# OptimuxPrimeEnlarged.net
KiCad netlist of a schematic drawn in EAGLE
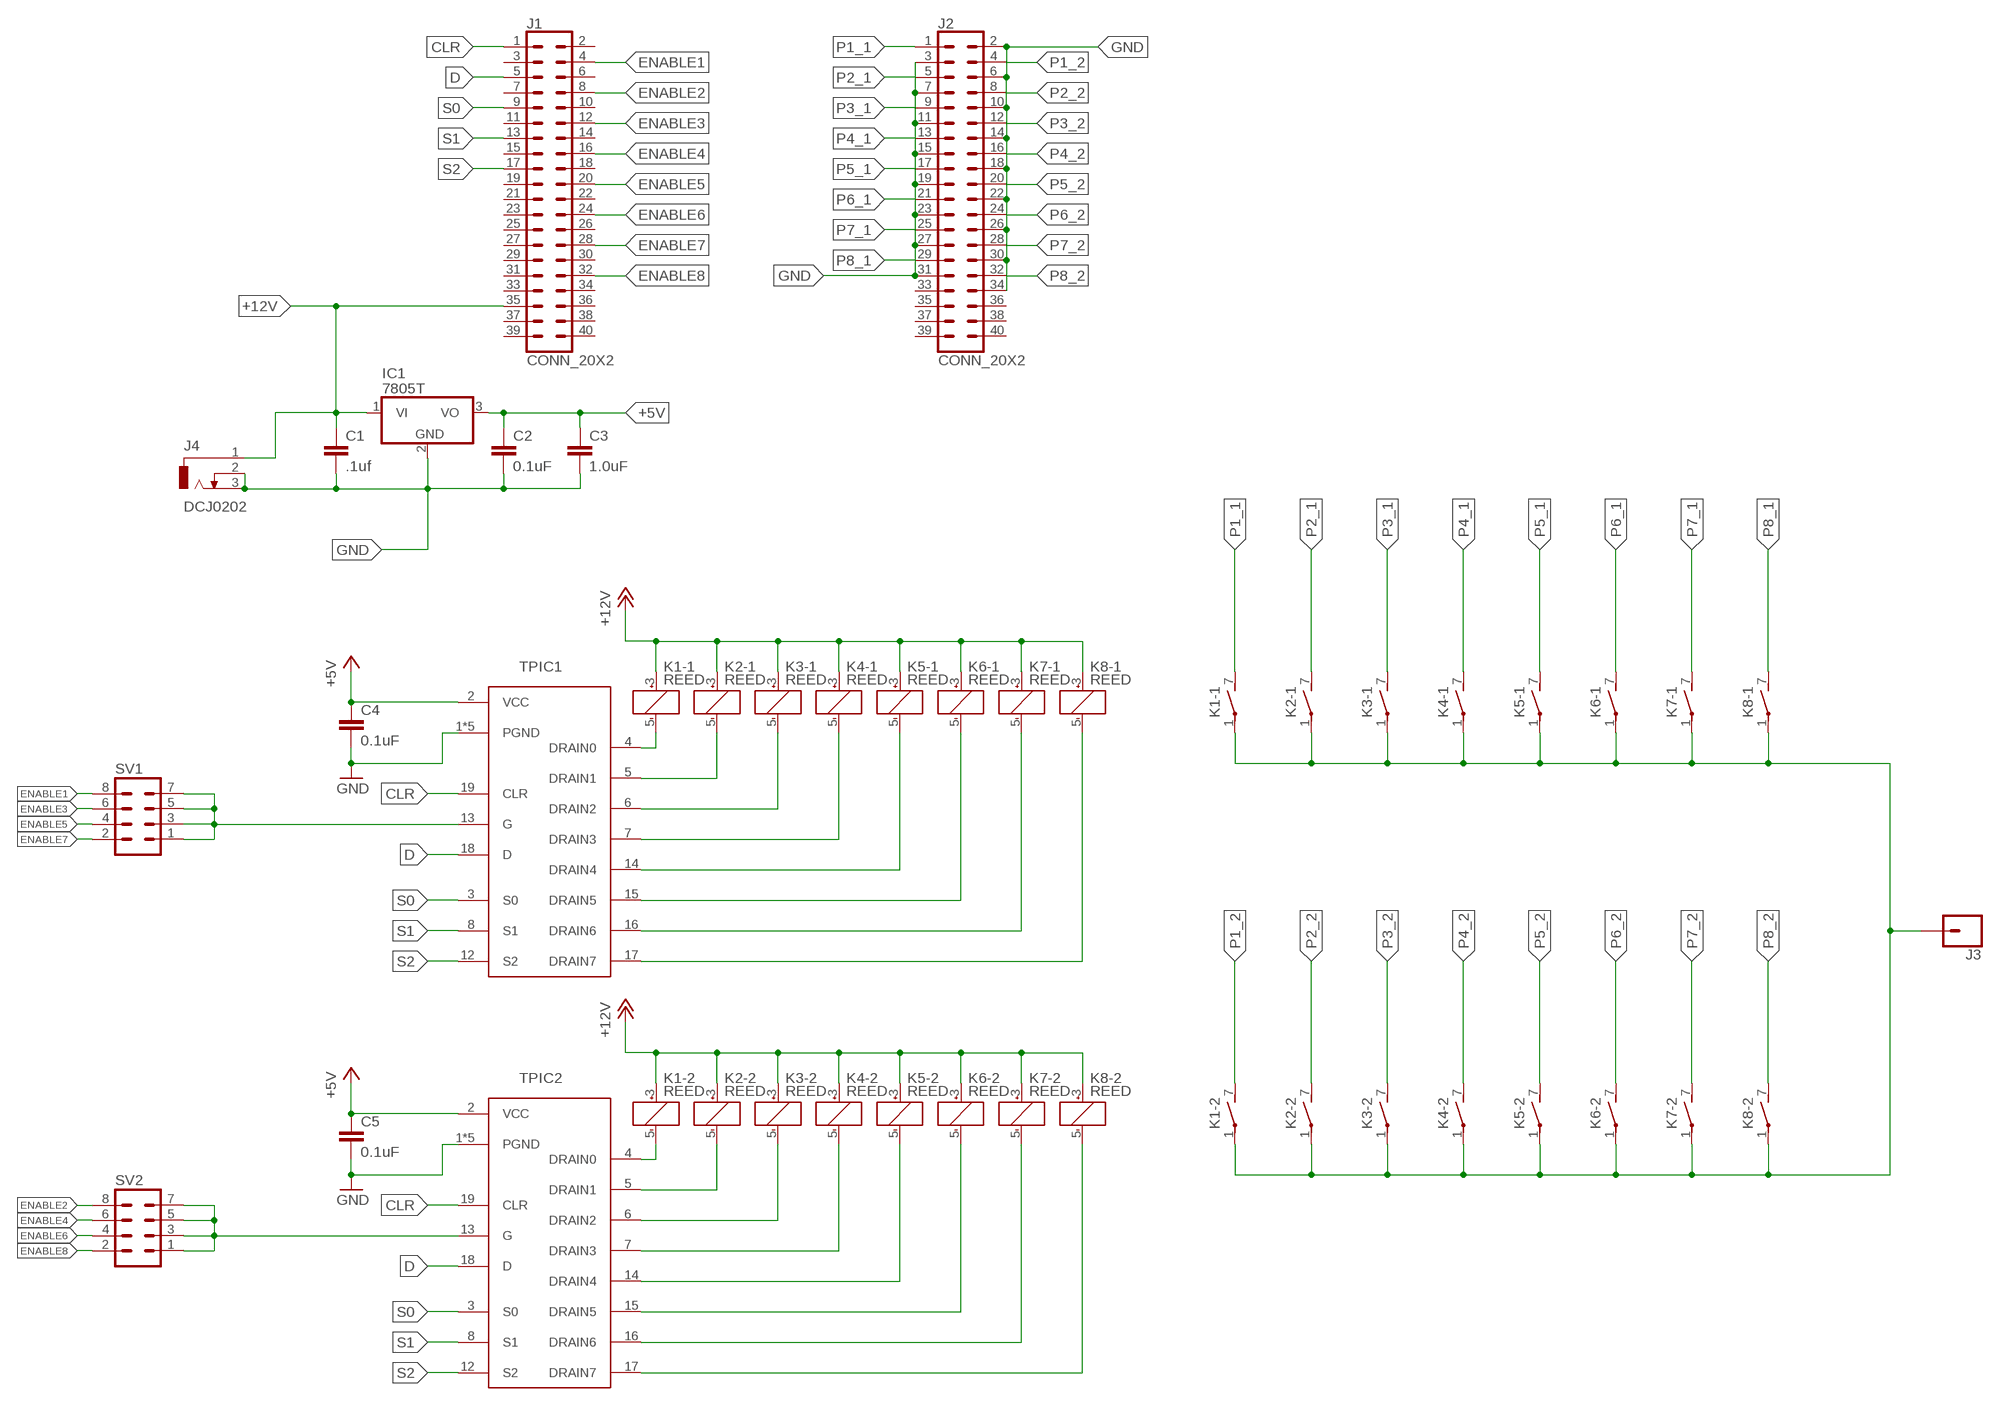
[diagram p0: schematic, sheet 1]

(export (version "E")
  (design (tool "Eeschema 10.0.6"))
  (components
    (comp (ref "C1")
      (value ".1uf")
      (footprint "eagle-import:0805")
      (libsource (lib "eagle-import") (part "1.0UF-0805-25V-(+80/-20%)"))
    )
    (comp (ref "C2")
      (value "0.1uF")
      (footprint "eagle-import:0805")
      (libsource (lib "eagle-import") (part "1.0UF-0805-25V-(+80/-20%)"))
    )
    (comp (ref "C3")
      (value "1.0uF")
      (footprint "eagle-import:0805")
      (libsource (lib "eagle-import") (part "1.0UF-0805-25V-(+80/-20%)"))
    )
    (comp (ref "C4")
      (value "0.1uF")
      (footprint "eagle-import:0805")
      (libsource (lib "eagle-import") (part "1.0UF-0805-25V-(+80/-20%)"))
    )
    (comp (ref "C5")
      (value "0.1uF")
      (footprint "eagle-import:0805")
      (libsource (lib "eagle-import") (part "1.0UF-0805-25V-(+80/-20%)"))
    )
    (comp (ref "IC1")
      (value "7805T")
      (footprint "eagle-import:TO220H")
      (libsource (lib "eagle-import") (part "78T05"))
    )
    (comp (ref "J1")
      (value "CONN_20X2")
      (footprint "eagle-import:2X20")
      (libsource (lib "eagle-import") (part "CONN_20X2"))
    )
    (comp (ref "J2")
      (value "CONN_20X2")
      (footprint "eagle-import:2X20")
      (libsource (lib "eagle-import") (part "CONN_20X2"))
    )
    (comp (ref "J3")
      (value "CONN_01")
      (footprint "eagle-import:1X01")
      (libsource (lib "eagle-import") (part "CONN_01"))
    )
    (comp (ref "J4")
      (value "DCJ0202")
      (footprint "eagle-import:DCJ0202")
      (libsource (lib "eagle-import") (part "DCJ0202"))
    )
    (comp (ref "K1-1")
      (value "REED")
      (footprint "eagle-import:REED")
      (libsource (lib "eagle-import") (part "REED"))
    )
    (comp (ref "K1-2")
      (value "REED")
      (footprint "eagle-import:REED")
      (libsource (lib "eagle-import") (part "REED"))
    )
    (comp (ref "K2-1")
      (value "REED")
      (footprint "eagle-import:REED")
      (libsource (lib "eagle-import") (part "REED"))
    )
    (comp (ref "K2-2")
      (value "REED")
      (footprint "eagle-import:REED")
      (libsource (lib "eagle-import") (part "REED"))
    )
    (comp (ref "K3-1")
      (value "REED")
      (footprint "eagle-import:REED")
      (libsource (lib "eagle-import") (part "REED"))
    )
    (comp (ref "K3-2")
      (value "REED")
      (footprint "eagle-import:REED")
      (libsource (lib "eagle-import") (part "REED"))
    )
    (comp (ref "K4-1")
      (value "REED")
      (footprint "eagle-import:REED")
      (libsource (lib "eagle-import") (part "REED"))
    )
    (comp (ref "K4-2")
      (value "REED")
      (footprint "eagle-import:REED")
      (libsource (lib "eagle-import") (part "REED"))
    )
    (comp (ref "K5-1")
      (value "REED")
      (footprint "eagle-import:REED")
      (libsource (lib "eagle-import") (part "REED"))
    )
    (comp (ref "K5-2")
      (value "REED")
      (footprint "eagle-import:REED")
      (libsource (lib "eagle-import") (part "REED"))
    )
    (comp (ref "K6-1")
      (value "REED")
      (footprint "eagle-import:REED")
      (libsource (lib "eagle-import") (part "REED"))
    )
    (comp (ref "K6-2")
      (value "REED")
      (footprint "eagle-import:REED")
      (libsource (lib "eagle-import") (part "REED"))
    )
    (comp (ref "K7-1")
      (value "REED")
      (footprint "eagle-import:REED")
      (libsource (lib "eagle-import") (part "REED"))
    )
    (comp (ref "K7-2")
      (value "REED")
      (footprint "eagle-import:REED")
      (libsource (lib "eagle-import") (part "REED"))
    )
    (comp (ref "K8-1")
      (value "REED")
      (footprint "eagle-import:REED")
      (libsource (lib "eagle-import") (part "REED"))
    )
    (comp (ref "K8-2")
      (value "REED")
      (footprint "eagle-import:REED")
      (libsource (lib "eagle-import") (part "REED"))
    )
    (comp (ref "SV1")
      (value "MA04-2")
      (footprint "eagle-import:MA04-2")
      (libsource (lib "eagle-import") (part "MA04-2"))
    )
    (comp (ref "SV2")
      (value "MA04-2")
      (footprint "eagle-import:MA04-2")
      (libsource (lib "eagle-import") (part "MA04-2"))
    )
    (comp (ref "TPIC1")
      (value "TPIC6259")
      (footprint "eagle-import:DIL20")
      (libsource (lib "eagle-import") (part "TPIC6259"))
    )
    (comp (ref "TPIC2")
      (value "TPIC6259")
      (footprint "eagle-import:DIL20")
      (libsource (lib "eagle-import") (part "TPIC6259"))
    )
  )
  (nets
    (net (code "1") (name "+5V") (class "Default")
      (node (ref "C2") (pin "1") (pinfunction "1_1") (pintype "passive"))
      (node (ref "C3") (pin "1") (pinfunction "1_1") (pintype "passive"))
      (node (ref "C4") (pin "1") (pinfunction "1_1") (pintype "passive"))
      (node (ref "C5") (pin "1") (pinfunction "1_1") (pintype "passive"))
      (node (ref "IC1") (pin "3") (pinfunction "VO_3") (pintype "passive"))
      (node (ref "TPIC1") (pin "2") (pinfunction "VCC_2") (pintype "bidirectional"))
      (node (ref "TPIC2") (pin "2") (pinfunction "VCC_2") (pintype "bidirectional"))
    )
    (net (code "2") (name "+12V") (class "Default")
      (node (ref "C1") (pin "1") (pinfunction "1_1") (pintype "passive"))
      (node (ref "IC1") (pin "1") (pinfunction "VI_1") (pintype "input"))
      (node (ref "J1") (pin "35") (pinfunction "35_35") (pintype "passive"))
      (node (ref "J4") (pin "1") (pinfunction "1_1") (pintype "passive"))
      (node (ref "K1-1") (pin "3") (pinfunction "+_3") (pintype "passive"))
      (node (ref "K1-2") (pin "3") (pinfunction "+_3") (pintype "passive"))
      (node (ref "K2-1") (pin "3") (pinfunction "+_3") (pintype "passive"))
      (node (ref "K2-2") (pin "3") (pinfunction "+_3") (pintype "passive"))
      (node (ref "K3-1") (pin "3") (pinfunction "+_3") (pintype "passive"))
      (node (ref "K3-2") (pin "3") (pinfunction "+_3") (pintype "passive"))
      (node (ref "K4-1") (pin "3") (pinfunction "+_3") (pintype "passive"))
      (node (ref "K4-2") (pin "3") (pinfunction "+_3") (pintype "passive"))
      (node (ref "K5-1") (pin "3") (pinfunction "+_3") (pintype "passive"))
      (node (ref "K5-2") (pin "3") (pinfunction "+_3") (pintype "passive"))
      (node (ref "K6-1") (pin "3") (pinfunction "+_3") (pintype "passive"))
      (node (ref "K6-2") (pin "3") (pinfunction "+_3") (pintype "passive"))
      (node (ref "K7-1") (pin "3") (pinfunction "+_3") (pintype "passive"))
      (node (ref "K7-2") (pin "3") (pinfunction "+_3") (pintype "passive"))
      (node (ref "K8-1") (pin "3") (pinfunction "+_3") (pintype "passive"))
      (node (ref "K8-2") (pin "3") (pinfunction "+_3") (pintype "passive"))
    )
    (net (code "3") (name "CLR") (class "Default")
      (node (ref "J1") (pin "1") (pinfunction "1_1") (pintype "passive"))
      (node (ref "TPIC1") (pin "19") (pinfunction "CLR_19") (pintype "bidirectional"))
      (node (ref "TPIC2") (pin "19") (pinfunction "CLR_19") (pintype "bidirectional"))
    )
    (net (code "4") (name "D") (class "Default")
      (node (ref "J1") (pin "5") (pinfunction "5_5") (pintype "passive"))
      (node (ref "TPIC1") (pin "18") (pinfunction "D_18") (pintype "bidirectional"))
      (node (ref "TPIC2") (pin "18") (pinfunction "D_18") (pintype "bidirectional"))
    )
    (net (code "5") (name "ENABLE1") (class "Default")
      (node (ref "J1") (pin "4") (pinfunction "4_4") (pintype "passive"))
      (node (ref "SV1") (pin "8") (pinfunction "8_8") (pintype "passive"))
    )
    (net (code "6") (name "ENABLE2") (class "Default")
      (node (ref "J1") (pin "8") (pinfunction "8_8") (pintype "passive"))
      (node (ref "SV2") (pin "8") (pinfunction "8_8") (pintype "passive"))
    )
    (net (code "7") (name "ENABLE3") (class "Default")
      (node (ref "J1") (pin "12") (pinfunction "12_12") (pintype "passive"))
      (node (ref "SV1") (pin "6") (pinfunction "6_6") (pintype "passive"))
    )
    (net (code "8") (name "ENABLE4") (class "Default")
      (node (ref "J1") (pin "16") (pinfunction "16_16") (pintype "passive"))
      (node (ref "SV2") (pin "6") (pinfunction "6_6") (pintype "passive"))
    )
    (net (code "9") (name "ENABLE5") (class "Default")
      (node (ref "J1") (pin "20") (pinfunction "20_20") (pintype "passive"))
      (node (ref "SV1") (pin "4") (pinfunction "4_4") (pintype "passive"))
    )
    (net (code "10") (name "ENABLE6") (class "Default")
      (node (ref "J1") (pin "24") (pinfunction "24_24") (pintype "passive"))
      (node (ref "SV2") (pin "4") (pinfunction "4_4") (pintype "passive"))
    )
    (net (code "11") (name "ENABLE7") (class "Default")
      (node (ref "J1") (pin "28") (pinfunction "28_28") (pintype "passive"))
      (node (ref "SV1") (pin "2") (pinfunction "2_2") (pintype "passive"))
    )
    (net (code "12") (name "ENABLE8") (class "Default")
      (node (ref "J1") (pin "32") (pinfunction "32_32") (pintype "passive"))
      (node (ref "SV2") (pin "2") (pinfunction "2_2") (pintype "passive"))
    )
    (net (code "13") (name "GND") (class "Default")
      (node (ref "C1") (pin "2") (pinfunction "2_2") (pintype "passive"))
      (node (ref "C2") (pin "2") (pinfunction "2_2") (pintype "passive"))
      (node (ref "C3") (pin "2") (pinfunction "2_2") (pintype "passive"))
      (node (ref "C4") (pin "2") (pinfunction "2_2") (pintype "passive"))
      (node (ref "C5") (pin "2") (pinfunction "2_2") (pintype "passive"))
      (node (ref "IC1") (pin "2") (pinfunction "GND_2") (pintype "passive"))
      (node (ref "J2") (pin "10") (pinfunction "10_10") (pintype "passive"))
      (node (ref "J2") (pin "11") (pinfunction "11_11") (pintype "passive"))
      (node (ref "J2") (pin "14") (pinfunction "14_14") (pintype "passive"))
      (node (ref "J2") (pin "15") (pinfunction "15_15") (pintype "passive"))
      (node (ref "J2") (pin "18") (pinfunction "18_18") (pintype "passive"))
      (node (ref "J2") (pin "19") (pinfunction "19_19") (pintype "passive"))
      (node (ref "J2") (pin "2") (pinfunction "2_2") (pintype "passive"))
      (node (ref "J2") (pin "22") (pinfunction "22_22") (pintype "passive"))
      (node (ref "J2") (pin "23") (pinfunction "23_23") (pintype "passive"))
      (node (ref "J2") (pin "26") (pinfunction "26_26") (pintype "passive"))
      (node (ref "J2") (pin "27") (pinfunction "27_27") (pintype "passive"))
      (node (ref "J2") (pin "3") (pinfunction "3_3") (pintype "passive"))
      (node (ref "J2") (pin "30") (pinfunction "30_30") (pintype "passive"))
      (node (ref "J2") (pin "31") (pinfunction "31_31") (pintype "passive"))
      (node (ref "J2") (pin "34") (pinfunction "34_34") (pintype "passive"))
      (node (ref "J2") (pin "6") (pinfunction "6_6") (pintype "passive"))
      (node (ref "J2") (pin "7") (pinfunction "7_7") (pintype "passive"))
      (node (ref "J4") (pin "2") (pinfunction "2_2") (pintype "passive"))
      (node (ref "J4") (pin "3") (pinfunction "3_3") (pintype "passive"))
      (node (ref "TPIC1") (pin "1") (pinfunction "PGND_1") (pintype "bidirectional"))
      (node (ref "TPIC1") (pin "10") (pinfunction "PGND_10") (pintype "bidirectional"))
      (node (ref "TPIC1") (pin "11") (pinfunction "PGND_11") (pintype "bidirectional"))
      (node (ref "TPIC1") (pin "20") (pinfunction "PGND_20") (pintype "bidirectional"))
      (node (ref "TPIC1") (pin "9") (pinfunction "PGND_9") (pintype "bidirectional"))
      (node (ref "TPIC2") (pin "1") (pinfunction "PGND_1") (pintype "bidirectional"))
      (node (ref "TPIC2") (pin "10") (pinfunction "PGND_10") (pintype "bidirectional"))
      (node (ref "TPIC2") (pin "11") (pinfunction "PGND_11") (pintype "bidirectional"))
      (node (ref "TPIC2") (pin "20") (pinfunction "PGND_20") (pintype "bidirectional"))
      (node (ref "TPIC2") (pin "9") (pinfunction "PGND_9") (pintype "bidirectional"))
    )
    (net (code "14") (name "Net-(K1-1A--)") (class "Default")
      (node (ref "K1-1") (pin "5") (pinfunction "-_5") (pintype "passive"))
      (node (ref "TPIC1") (pin "4") (pinfunction "DRAIN0_4") (pintype "bidirectional"))
    )
    (net (code "15") (name "Net-(K1-1B-P)") (class "Default")
      (node (ref "J3") (pin "1") (pinfunction "1_1") (pintype "passive"))
      (node (ref "K1-1") (pin "1") (pinfunction "P_1") (pintype "passive"))
      (node (ref "K1-2") (pin "1") (pinfunction "P_1") (pintype "passive"))
      (node (ref "K2-1") (pin "1") (pinfunction "P_1") (pintype "passive"))
      (node (ref "K2-2") (pin "1") (pinfunction "P_1") (pintype "passive"))
      (node (ref "K3-1") (pin "1") (pinfunction "P_1") (pintype "passive"))
      (node (ref "K3-2") (pin "1") (pinfunction "P_1") (pintype "passive"))
      (node (ref "K4-1") (pin "1") (pinfunction "P_1") (pintype "passive"))
      (node (ref "K4-2") (pin "1") (pinfunction "P_1") (pintype "passive"))
      (node (ref "K5-1") (pin "1") (pinfunction "P_1") (pintype "passive"))
      (node (ref "K5-2") (pin "1") (pinfunction "P_1") (pintype "passive"))
      (node (ref "K6-1") (pin "1") (pinfunction "P_1") (pintype "passive"))
      (node (ref "K6-2") (pin "1") (pinfunction "P_1") (pintype "passive"))
      (node (ref "K7-1") (pin "1") (pinfunction "P_1") (pintype "passive"))
      (node (ref "K7-2") (pin "1") (pinfunction "P_1") (pintype "passive"))
      (node (ref "K8-1") (pin "1") (pinfunction "P_1") (pintype "passive"))
      (node (ref "K8-2") (pin "1") (pinfunction "P_1") (pintype "passive"))
    )
    (net (code "16") (name "Net-(K1-2A--)") (class "Default")
      (node (ref "K1-2") (pin "5") (pinfunction "-_5") (pintype "passive"))
      (node (ref "TPIC2") (pin "4") (pinfunction "DRAIN0_4") (pintype "bidirectional"))
    )
    (net (code "17") (name "Net-(K2-1A--)") (class "Default")
      (node (ref "K2-1") (pin "5") (pinfunction "-_5") (pintype "passive"))
      (node (ref "TPIC1") (pin "5") (pinfunction "DRAIN1_5") (pintype "bidirectional"))
    )
    (net (code "18") (name "Net-(K2-2A--)") (class "Default")
      (node (ref "K2-2") (pin "5") (pinfunction "-_5") (pintype "passive"))
      (node (ref "TPIC2") (pin "5") (pinfunction "DRAIN1_5") (pintype "bidirectional"))
    )
    (net (code "19") (name "Net-(K3-1A--)") (class "Default")
      (node (ref "K3-1") (pin "5") (pinfunction "-_5") (pintype "passive"))
      (node (ref "TPIC1") (pin "6") (pinfunction "DRAIN2_6") (pintype "bidirectional"))
    )
    (net (code "20") (name "Net-(K3-2A--)") (class "Default")
      (node (ref "K3-2") (pin "5") (pinfunction "-_5") (pintype "passive"))
      (node (ref "TPIC2") (pin "6") (pinfunction "DRAIN2_6") (pintype "bidirectional"))
    )
    (net (code "21") (name "Net-(K4-1A--)") (class "Default")
      (node (ref "K4-1") (pin "5") (pinfunction "-_5") (pintype "passive"))
      (node (ref "TPIC1") (pin "7") (pinfunction "DRAIN3_7") (pintype "bidirectional"))
    )
    (net (code "22") (name "Net-(K4-2A--)") (class "Default")
      (node (ref "K4-2") (pin "5") (pinfunction "-_5") (pintype "passive"))
      (node (ref "TPIC2") (pin "7") (pinfunction "DRAIN3_7") (pintype "bidirectional"))
    )
    (net (code "23") (name "Net-(K5-1A--)") (class "Default")
      (node (ref "K5-1") (pin "5") (pinfunction "-_5") (pintype "passive"))
      (node (ref "TPIC1") (pin "14") (pinfunction "DRAIN4_14") (pintype "bidirectional"))
    )
    (net (code "24") (name "Net-(K5-2A--)") (class "Default")
      (node (ref "K5-2") (pin "5") (pinfunction "-_5") (pintype "passive"))
      (node (ref "TPIC2") (pin "14") (pinfunction "DRAIN4_14") (pintype "bidirectional"))
    )
    (net (code "25") (name "Net-(K6-1A--)") (class "Default")
      (node (ref "K6-1") (pin "5") (pinfunction "-_5") (pintype "passive"))
      (node (ref "TPIC1") (pin "15") (pinfunction "DRAIN5_15") (pintype "bidirectional"))
    )
    (net (code "26") (name "Net-(K6-2A--)") (class "Default")
      (node (ref "K6-2") (pin "5") (pinfunction "-_5") (pintype "passive"))
      (node (ref "TPIC2") (pin "15") (pinfunction "DRAIN5_15") (pintype "bidirectional"))
    )
    (net (code "27") (name "Net-(K7-1A--)") (class "Default")
      (node (ref "K7-1") (pin "5") (pinfunction "-_5") (pintype "passive"))
      (node (ref "TPIC1") (pin "16") (pinfunction "DRAIN6_16") (pintype "bidirectional"))
    )
    (net (code "28") (name "Net-(K7-2A--)") (class "Default")
      (node (ref "K7-2") (pin "5") (pinfunction "-_5") (pintype "passive"))
      (node (ref "TPIC2") (pin "16") (pinfunction "DRAIN6_16") (pintype "bidirectional"))
    )
    (net (code "29") (name "Net-(K8-1A--)") (class "Default")
      (node (ref "K8-1") (pin "5") (pinfunction "-_5") (pintype "passive"))
      (node (ref "TPIC1") (pin "17") (pinfunction "DRAIN7_17") (pintype "bidirectional"))
    )
    (net (code "30") (name "Net-(K8-2A--)") (class "Default")
      (node (ref "K8-2") (pin "5") (pinfunction "-_5") (pintype "passive"))
      (node (ref "TPIC2") (pin "17") (pinfunction "DRAIN7_17") (pintype "bidirectional"))
    )
    (net (code "31") (name "Net-(TPIC1-G)") (class "Default")
      (node (ref "SV1") (pin "1") (pinfunction "1_1") (pintype "passive"))
      (node (ref "SV1") (pin "3") (pinfunction "3_3") (pintype "passive"))
      (node (ref "SV1") (pin "5") (pinfunction "5_5") (pintype "passive"))
      (node (ref "SV1") (pin "7") (pinfunction "7_7") (pintype "passive"))
      (node (ref "TPIC1") (pin "13") (pinfunction "G_13") (pintype "bidirectional"))
    )
    (net (code "32") (name "Net-(TPIC2-G)") (class "Default")
      (node (ref "SV2") (pin "1") (pinfunction "1_1") (pintype "passive"))
      (node (ref "SV2") (pin "3") (pinfunction "3_3") (pintype "passive"))
      (node (ref "SV2") (pin "5") (pinfunction "5_5") (pintype "passive"))
      (node (ref "SV2") (pin "7") (pinfunction "7_7") (pintype "passive"))
      (node (ref "TPIC2") (pin "13") (pinfunction "G_13") (pintype "bidirectional"))
    )
    (net (code "33") (name "P1_1") (class "Default")
      (node (ref "J2") (pin "1") (pinfunction "1_1") (pintype "passive"))
      (node (ref "K1-1") (pin "7") (pinfunction "S_7") (pintype "passive"))
    )
    (net (code "34") (name "P1_2") (class "Default")
      (node (ref "J2") (pin "4") (pinfunction "4_4") (pintype "passive"))
      (node (ref "K1-2") (pin "7") (pinfunction "S_7") (pintype "passive"))
    )
    (net (code "35") (name "P2_1") (class "Default")
      (node (ref "J2") (pin "5") (pinfunction "5_5") (pintype "passive"))
      (node (ref "K2-1") (pin "7") (pinfunction "S_7") (pintype "passive"))
    )
    (net (code "36") (name "P2_2") (class "Default")
      (node (ref "J2") (pin "8") (pinfunction "8_8") (pintype "passive"))
      (node (ref "K2-2") (pin "7") (pinfunction "S_7") (pintype "passive"))
    )
    (net (code "37") (name "P3_1") (class "Default")
      (node (ref "J2") (pin "9") (pinfunction "9_9") (pintype "passive"))
      (node (ref "K3-1") (pin "7") (pinfunction "S_7") (pintype "passive"))
    )
    (net (code "38") (name "P3_2") (class "Default")
      (node (ref "J2") (pin "12") (pinfunction "12_12") (pintype "passive"))
      (node (ref "K3-2") (pin "7") (pinfunction "S_7") (pintype "passive"))
    )
    (net (code "39") (name "P4_1") (class "Default")
      (node (ref "J2") (pin "13") (pinfunction "13_13") (pintype "passive"))
      (node (ref "K4-1") (pin "7") (pinfunction "S_7") (pintype "passive"))
    )
    (net (code "40") (name "P4_2") (class "Default")
      (node (ref "J2") (pin "16") (pinfunction "16_16") (pintype "passive"))
      (node (ref "K4-2") (pin "7") (pinfunction "S_7") (pintype "passive"))
    )
    (net (code "41") (name "P5_1") (class "Default")
      (node (ref "J2") (pin "17") (pinfunction "17_17") (pintype "passive"))
      (node (ref "K5-1") (pin "7") (pinfunction "S_7") (pintype "passive"))
    )
    (net (code "42") (name "P5_2") (class "Default")
      (node (ref "J2") (pin "20") (pinfunction "20_20") (pintype "passive"))
      (node (ref "K5-2") (pin "7") (pinfunction "S_7") (pintype "passive"))
    )
    (net (code "43") (name "P6_1") (class "Default")
      (node (ref "J2") (pin "21") (pinfunction "21_21") (pintype "passive"))
      (node (ref "K6-1") (pin "7") (pinfunction "S_7") (pintype "passive"))
    )
    (net (code "44") (name "P6_2") (class "Default")
      (node (ref "J2") (pin "24") (pinfunction "24_24") (pintype "passive"))
      (node (ref "K6-2") (pin "7") (pinfunction "S_7") (pintype "passive"))
    )
    (net (code "45") (name "P7_1") (class "Default")
      (node (ref "J2") (pin "25") (pinfunction "25_25") (pintype "passive"))
      (node (ref "K7-1") (pin "7") (pinfunction "S_7") (pintype "passive"))
    )
    (net (code "46") (name "P7_2") (class "Default")
      (node (ref "J2") (pin "28") (pinfunction "28_28") (pintype "passive"))
      (node (ref "K7-2") (pin "7") (pinfunction "S_7") (pintype "passive"))
    )
    (net (code "47") (name "P8_1") (class "Default")
      (node (ref "J2") (pin "29") (pinfunction "29_29") (pintype "passive"))
      (node (ref "K8-1") (pin "7") (pinfunction "S_7") (pintype "passive"))
    )
    (net (code "48") (name "P8_2") (class "Default")
      (node (ref "J2") (pin "32") (pinfunction "32_32") (pintype "passive"))
      (node (ref "K8-2") (pin "7") (pinfunction "S_7") (pintype "passive"))
    )
    (net (code "49") (name "S0") (class "Default")
      (node (ref "J1") (pin "9") (pinfunction "9_9") (pintype "passive"))
      (node (ref "TPIC1") (pin "3") (pinfunction "S0_3") (pintype "bidirectional"))
      (node (ref "TPIC2") (pin "3") (pinfunction "S0_3") (pintype "bidirectional"))
    )
    (net (code "50") (name "S1") (class "Default")
      (node (ref "J1") (pin "13") (pinfunction "13_13") (pintype "passive"))
      (node (ref "TPIC1") (pin "8") (pinfunction "S1_8") (pintype "bidirectional"))
      (node (ref "TPIC2") (pin "8") (pinfunction "S1_8") (pintype "bidirectional"))
    )
    (net (code "51") (name "S2") (class "Default")
      (node (ref "J1") (pin "17") (pinfunction "17_17") (pintype "passive"))
      (node (ref "TPIC1") (pin "12") (pinfunction "S2_12") (pintype "bidirectional"))
      (node (ref "TPIC2") (pin "12") (pinfunction "S2_12") (pintype "bidirectional"))
    )
    (net (code "52") (name "unconnected-(J1-Pad2)") (class "Default")
      (node (ref "J1") (pin "2") (pinfunction "2_2") (pintype "passive"))
    )
    (net (code "53") (name "unconnected-(J1-Pad3)") (class "Default")
      (node (ref "J1") (pin "3") (pinfunction "3_3") (pintype "passive"))
    )
    (net (code "54") (name "unconnected-(J1-Pad6)") (class "Default")
      (node (ref "J1") (pin "6") (pinfunction "6_6") (pintype "passive"))
    )
    (net (code "55") (name "unconnected-(J1-Pad7)") (class "Default")
      (node (ref "J1") (pin "7") (pinfunction "7_7") (pintype "passive"))
    )
    (net (code "56") (name "unconnected-(J1-Pad10)") (class "Default")
      (node (ref "J1") (pin "10") (pinfunction "10_10") (pintype "passive"))
    )
    (net (code "57") (name "unconnected-(J1-Pad11)") (class "Default")
      (node (ref "J1") (pin "11") (pinfunction "11_11") (pintype "passive"))
    )
    (net (code "58") (name "unconnected-(J1-Pad14)") (class "Default")
      (node (ref "J1") (pin "14") (pinfunction "14_14") (pintype "passive"))
    )
    (net (code "59") (name "unconnected-(J1-Pad15)") (class "Default")
      (node (ref "J1") (pin "15") (pinfunction "15_15") (pintype "passive"))
    )
    (net (code "60") (name "unconnected-(J1-Pad18)") (class "Default")
      (node (ref "J1") (pin "18") (pinfunction "18_18") (pintype "passive"))
    )
    (net (code "61") (name "unconnected-(J1-Pad19)") (class "Default")
      (node (ref "J1") (pin "19") (pinfunction "19_19") (pintype "passive"))
    )
    (net (code "62") (name "unconnected-(J1-Pad21)") (class "Default")
      (node (ref "J1") (pin "21") (pinfunction "21_21") (pintype "passive"))
    )
    (net (code "63") (name "unconnected-(J1-Pad22)") (class "Default")
      (node (ref "J1") (pin "22") (pinfunction "22_22") (pintype "passive"))
    )
    (net (code "64") (name "unconnected-(J1-Pad23)") (class "Default")
      (node (ref "J1") (pin "23") (pinfunction "23_23") (pintype "passive"))
    )
    (net (code "65") (name "unconnected-(J1-Pad25)") (class "Default")
      (node (ref "J1") (pin "25") (pinfunction "25_25") (pintype "passive"))
    )
    (net (code "66") (name "unconnected-(J1-Pad26)") (class "Default")
      (node (ref "J1") (pin "26") (pinfunction "26_26") (pintype "passive"))
    )
    (net (code "67") (name "unconnected-(J1-Pad27)") (class "Default")
      (node (ref "J1") (pin "27") (pinfunction "27_27") (pintype "passive"))
    )
    (net (code "68") (name "unconnected-(J1-Pad29)") (class "Default")
      (node (ref "J1") (pin "29") (pinfunction "29_29") (pintype "passive"))
    )
    (net (code "69") (name "unconnected-(J1-Pad30)") (class "Default")
      (node (ref "J1") (pin "30") (pinfunction "30_30") (pintype "passive"))
    )
    (net (code "70") (name "unconnected-(J1-Pad31)") (class "Default")
      (node (ref "J1") (pin "31") (pinfunction "31_31") (pintype "passive"))
    )
    (net (code "71") (name "unconnected-(J1-Pad33)") (class "Default")
      (node (ref "J1") (pin "33") (pinfunction "33_33") (pintype "passive"))
    )
    (net (code "72") (name "unconnected-(J1-Pad34)") (class "Default")
      (node (ref "J1") (pin "34") (pinfunction "34_34") (pintype "passive"))
    )
    (net (code "73") (name "unconnected-(J1-Pad36)") (class "Default")
      (node (ref "J1") (pin "36") (pinfunction "36_36") (pintype "passive"))
    )
    (net (code "74") (name "unconnected-(J1-Pad37)") (class "Default")
      (node (ref "J1") (pin "37") (pinfunction "37_37") (pintype "passive"))
    )
    (net (code "75") (name "unconnected-(J1-Pad38)") (class "Default")
      (node (ref "J1") (pin "38") (pinfunction "38_38") (pintype "passive"))
    )
    (net (code "76") (name "unconnected-(J1-Pad39)") (class "Default")
      (node (ref "J1") (pin "39") (pinfunction "39_39") (pintype "passive"))
    )
    (net (code "77") (name "unconnected-(J1-Pad40)") (class "Default")
      (node (ref "J1") (pin "40") (pinfunction "40_40") (pintype "passive"))
    )
    (net (code "78") (name "unconnected-(J2-Pad33)") (class "Default")
      (node (ref "J2") (pin "33") (pinfunction "33_33") (pintype "passive"))
    )
    (net (code "79") (name "unconnected-(J2-Pad35)") (class "Default")
      (node (ref "J2") (pin "35") (pinfunction "35_35") (pintype "passive"))
    )
    (net (code "80") (name "unconnected-(J2-Pad36)") (class "Default")
      (node (ref "J2") (pin "36") (pinfunction "36_36") (pintype "passive"))
    )
    (net (code "81") (name "unconnected-(J2-Pad37)") (class "Default")
      (node (ref "J2") (pin "37") (pinfunction "37_37") (pintype "passive"))
    )
    (net (code "82") (name "unconnected-(J2-Pad38)") (class "Default")
      (node (ref "J2") (pin "38") (pinfunction "38_38") (pintype "passive"))
    )
    (net (code "83") (name "unconnected-(J2-Pad39)") (class "Default")
      (node (ref "J2") (pin "39") (pinfunction "39_39") (pintype "passive"))
    )
    (net (code "84") (name "unconnected-(J2-Pad40)") (class "Default")
      (node (ref "J2") (pin "40") (pinfunction "40_40") (pintype "passive"))
    )
  )
)
